# Magneto.net
KiCad netlist of a schematic drawn in Altium Designer
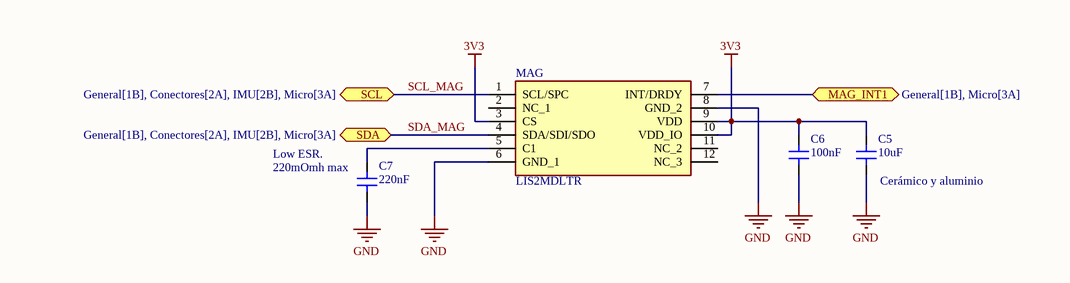
[diagram p0: Magneto.SchDoc]

(export (version "E")
  (design (tool "Eeschema 10.0.6"))
  (components
    (comp (ref "C5")
      (value "CAP_0805_100nF")
      (footprint "CAP SMD 0805")
      (description "Condensador 0805 100nF")
      (fields (field (name "VALOR") "10uF"))
      (libsource (lib "ARUS Electronica") (part "Symbol"))
    )
    (comp (ref "C6")
      (value "CAP_0805_100nF")
      (footprint "CAP SMD 0805")
      (description "Condensador 0805 100nF")
      (fields (field (name "VALOR") "100nF"))
      (libsource (lib "ARUS Electronica") (part "Symbol"))
    )
    (comp (ref "C7")
      (value "CAP_0805_100nF")
      (footprint "CAP SMD 0805")
      (description "Condensador 0805 100nF")
      (fields (field (name "VALOR") "220nF"))
      (libsource (lib "ARUS Electronica") (part "Symbol"))
    )
    (comp (ref "MAG")
      (value "LIS2MDLTR")
      (footprint "SamacSys:LGA-12")
      (description "Integrated Circuit")
      (fields (field (name "MOUSER PART NUMBER") "511-LIS2MDLTR"))
      (libsource (lib "*") (part "LIS2MDLTR"))
    )
  )
  (nets
    (net (code "1") (name "/MAG_INT1") (class "Default")
      (node (ref "MAG") (pin "7") (pinfunction "INT/DRDY_7") (pintype "passive"))
    )
    (net (code "2") (name "/SCL_MAG") (class "Default")
      (node (ref "MAG") (pin "1") (pinfunction "SCL/SPC_1") (pintype "passive"))
    )
    (net (code "3") (name "/SDA_MAG") (class "Default")
      (node (ref "MAG") (pin "4") (pinfunction "SDA/SDI/SDO_4") (pintype "passive"))
    )
    (net (code "4") (name "3V3") (class "Default")
      (node (ref "C5") (pin "2") (pinfunction "2_2") (pintype "passive"))
      (node (ref "C6") (pin "2") (pinfunction "2_2") (pintype "passive"))
      (node (ref "MAG") (pin "10") (pinfunction "VDD_IO_10") (pintype "passive"))
      (node (ref "MAG") (pin "3") (pinfunction "CS_3") (pintype "passive"))
      (node (ref "MAG") (pin "9") (pinfunction "VDD_9") (pintype "passive"))
    )
    (net (code "5") (name "GND") (class "Default")
      (node (ref "C5") (pin "1") (pinfunction "1_1") (pintype "passive"))
      (node (ref "C6") (pin "1") (pinfunction "1_1") (pintype "passive"))
      (node (ref "C7") (pin "2") (pinfunction "2_2") (pintype "passive"))
      (node (ref "MAG") (pin "6") (pinfunction "GND_1_6") (pintype "passive"))
      (node (ref "MAG") (pin "8") (pinfunction "GND_2_8") (pintype "passive"))
    )
    (net (code "6") (name "Net-(MAG-C1)") (class "Default")
      (node (ref "C7") (pin "1") (pinfunction "1_1") (pintype "passive"))
      (node (ref "MAG") (pin "5") (pinfunction "C1_5") (pintype "passive"))
    )
    (net (code "7") (name "unconnected-(MAG-NC_1-Pad2)") (class "Default")
      (node (ref "MAG") (pin "2") (pinfunction "NC_1_2") (pintype "passive"))
    )
    (net (code "8") (name "unconnected-(MAG-NC_2-Pad11)") (class "Default")
      (node (ref "MAG") (pin "11") (pinfunction "NC_2_11") (pintype "passive"))
    )
    (net (code "9") (name "unconnected-(MAG-NC_3-Pad12)") (class "Default")
      (node (ref "MAG") (pin "12") (pinfunction "NC_3_12") (pintype "passive"))
    )
  )
)
